# pengendali.net
KiCad netlist of a schematic drawn in EAGLE
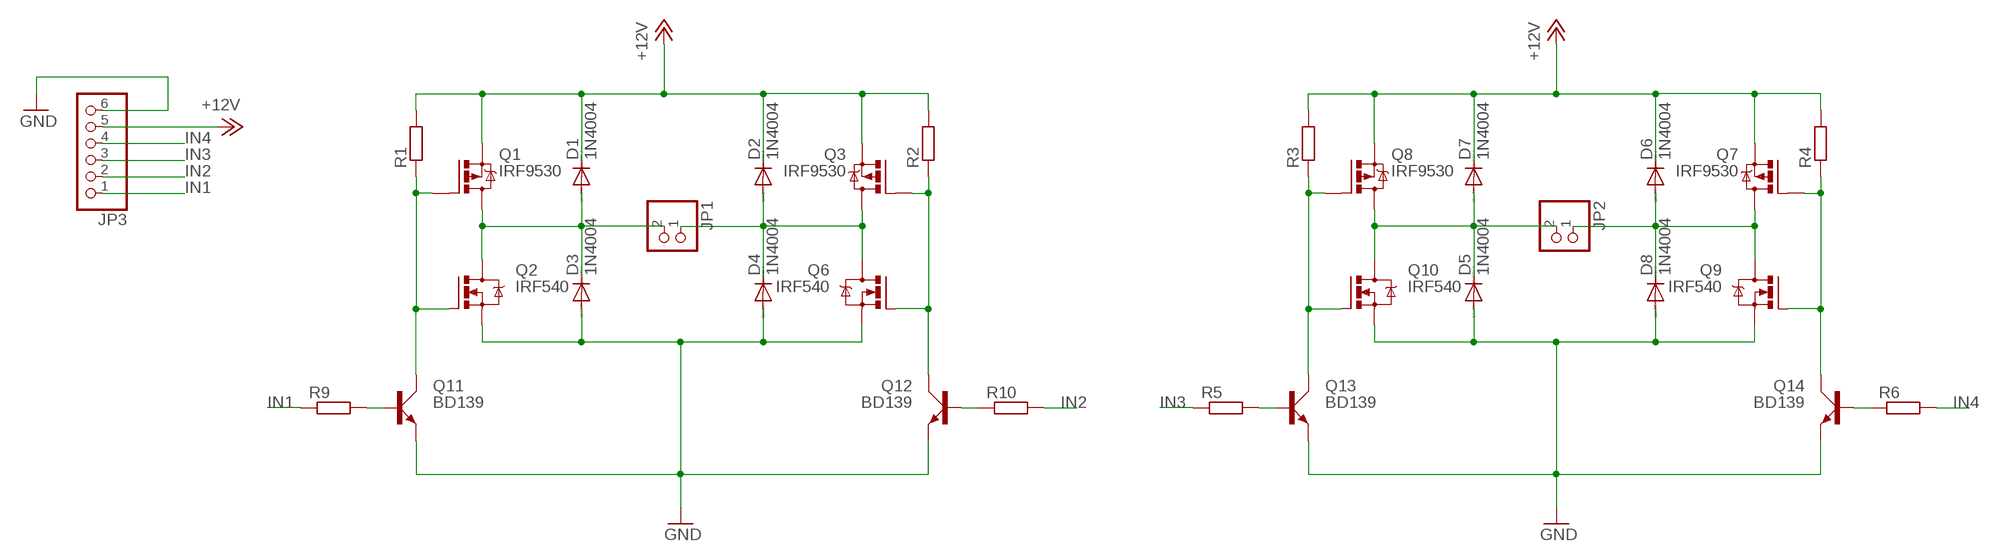
[diagram p0: schematic, sheet 1]

(export (version "E")
  (design (tool "Eeschema 10.0.6"))
  (components
    (comp (ref "D1")
      (value "1N4004")
      (footprint "eagle-import:DO41-10")
      (libsource (lib "eagle-import") (part "1N4004"))
    )
    (comp (ref "D2")
      (value "1N4004")
      (footprint "eagle-import:DO41-10")
      (libsource (lib "eagle-import") (part "1N4004"))
    )
    (comp (ref "D3")
      (value "1N4004")
      (footprint "eagle-import:DO41-10")
      (libsource (lib "eagle-import") (part "1N4004"))
    )
    (comp (ref "D4")
      (value "1N4004")
      (footprint "eagle-import:DO41-10")
      (libsource (lib "eagle-import") (part "1N4004"))
    )
    (comp (ref "D5")
      (value "1N4004")
      (footprint "eagle-import:DO41-10")
      (libsource (lib "eagle-import") (part "1N4004"))
    )
    (comp (ref "D6")
      (value "1N4004")
      (footprint "eagle-import:DO41-10")
      (libsource (lib "eagle-import") (part "1N4004"))
    )
    (comp (ref "D7")
      (value "1N4004")
      (footprint "eagle-import:DO41-10")
      (libsource (lib "eagle-import") (part "1N4004"))
    )
    (comp (ref "D8")
      (value "1N4004")
      (footprint "eagle-import:DO41-10")
      (libsource (lib "eagle-import") (part "1N4004"))
    )
    (comp (ref "JP1")
      (value "PINHD-1X2")
      (footprint "eagle-import:1X02")
      (libsource (lib "eagle-import") (part "PINHD-1X2"))
    )
    (comp (ref "JP2")
      (value "PINHD-1X2")
      (footprint "eagle-import:1X02")
      (libsource (lib "eagle-import") (part "PINHD-1X2"))
    )
    (comp (ref "JP3")
      (value "PINHD-1X6")
      (footprint "eagle-import:1X06")
      (libsource (lib "eagle-import") (part "PINHD-1X6"))
    )
    (comp (ref "Q1")
      (value "IRF9530")
      (footprint "eagle-import:TO220BV")
      (libsource (lib "eagle-import") (part "IRF9530"))
    )
    (comp (ref "Q2")
      (value "IRF540")
      (footprint "eagle-import:TO220BV")
      (libsource (lib "eagle-import") (part "IRF540"))
    )
    (comp (ref "Q3")
      (value "IRF9530")
      (footprint "eagle-import:TO220BV")
      (libsource (lib "eagle-import") (part "IRF9530"))
    )
    (comp (ref "Q6")
      (value "IRF540")
      (footprint "eagle-import:TO220BV")
      (libsource (lib "eagle-import") (part "IRF540"))
    )
    (comp (ref "Q7")
      (value "IRF9530")
      (footprint "eagle-import:TO220BV")
      (libsource (lib "eagle-import") (part "IRF9530"))
    )
    (comp (ref "Q8")
      (value "IRF9530")
      (footprint "eagle-import:TO220BV")
      (libsource (lib "eagle-import") (part "IRF9530"))
    )
    (comp (ref "Q9")
      (value "IRF540")
      (footprint "eagle-import:TO220BV")
      (libsource (lib "eagle-import") (part "IRF540"))
    )
    (comp (ref "Q10")
      (value "IRF540")
      (footprint "eagle-import:TO220BV")
      (libsource (lib "eagle-import") (part "IRF540"))
    )
    (comp (ref "Q11")
      (value "BD139")
      (footprint "eagle-import:TO126AV")
      (libsource (lib "eagle-import") (part "BD139"))
    )
    (comp (ref "Q12")
      (value "BD139")
      (footprint "eagle-import:TO126AV")
      (libsource (lib "eagle-import") (part "BD139"))
    )
    (comp (ref "Q13")
      (value "BD139")
      (footprint "eagle-import:TO126AV")
      (libsource (lib "eagle-import") (part "BD139"))
    )
    (comp (ref "Q14")
      (value "BD139")
      (footprint "eagle-import:TO126AV")
      (libsource (lib "eagle-import") (part "BD139"))
    )
    (comp (ref "R1")
      (value "R-EU_0204/7")
      (footprint "eagle-import:0204_7")
      (libsource (lib "eagle-import") (part "R-EU_0204/7"))
    )
    (comp (ref "R2")
      (value "R-EU_0204/7")
      (footprint "eagle-import:0204_7")
      (libsource (lib "eagle-import") (part "R-EU_0204/7"))
    )
    (comp (ref "R3")
      (value "R-EU_0204/7")
      (footprint "eagle-import:0204_7")
      (libsource (lib "eagle-import") (part "R-EU_0204/7"))
    )
    (comp (ref "R4")
      (value "R-EU_0204/7")
      (footprint "eagle-import:0204_7")
      (libsource (lib "eagle-import") (part "R-EU_0204/7"))
    )
    (comp (ref "R5")
      (value "R-EU_0204/7")
      (footprint "eagle-import:0204_7")
      (libsource (lib "eagle-import") (part "R-EU_0204/7"))
    )
    (comp (ref "R6")
      (value "R-EU_0204/7")
      (footprint "eagle-import:0204_7")
      (libsource (lib "eagle-import") (part "R-EU_0204/7"))
    )
    (comp (ref "R9")
      (value "R-EU_0204/7")
      (footprint "eagle-import:0204_7")
      (libsource (lib "eagle-import") (part "R-EU_0204/7"))
    )
    (comp (ref "R10")
      (value "R-EU_0204/7")
      (footprint "eagle-import:0204_7")
      (libsource (lib "eagle-import") (part "R-EU_0204/7"))
    )
  )
  (nets
    (net (code "1") (name "+12V") (class "Default")
      (node (ref "D1") (pin "C") (pinfunction "C_C") (pintype "passive"))
      (node (ref "D2") (pin "C") (pinfunction "C_C") (pintype "passive"))
      (node (ref "D6") (pin "C") (pinfunction "C_C") (pintype "passive"))
      (node (ref "D7") (pin "C") (pinfunction "C_C") (pintype "passive"))
      (node (ref "JP3") (pin "5") (pinfunction "5_5") (pintype "passive"))
      (node (ref "Q1") (pin "S") (pinfunction "S_S") (pintype "passive"))
      (node (ref "Q3") (pin "S") (pinfunction "S_S") (pintype "passive"))
      (node (ref "Q7") (pin "S") (pinfunction "S_S") (pintype "passive"))
      (node (ref "Q8") (pin "S") (pinfunction "S_S") (pintype "passive"))
      (node (ref "R1") (pin "2") (pinfunction "2_2") (pintype "passive"))
      (node (ref "R2") (pin "2") (pinfunction "2_2") (pintype "passive"))
      (node (ref "R3") (pin "2") (pinfunction "2_2") (pintype "passive"))
      (node (ref "R4") (pin "2") (pinfunction "2_2") (pintype "passive"))
    )
    (net (code "2") (name "/IN1") (class "Default")
      (node (ref "JP3") (pin "1") (pinfunction "1_1") (pintype "passive"))
      (node (ref "R9") (pin "1") (pinfunction "1_1") (pintype "passive"))
    )
    (net (code "3") (name "/IN2") (class "Default")
      (node (ref "JP3") (pin "2") (pinfunction "2_2") (pintype "passive"))
      (node (ref "R10") (pin "2") (pinfunction "2_2") (pintype "passive"))
    )
    (net (code "4") (name "/IN3") (class "Default")
      (node (ref "JP3") (pin "3") (pinfunction "3_3") (pintype "passive"))
      (node (ref "R5") (pin "1") (pinfunction "1_1") (pintype "passive"))
    )
    (net (code "5") (name "/IN4") (class "Default")
      (node (ref "JP3") (pin "4") (pinfunction "4_4") (pintype "passive"))
      (node (ref "R6") (pin "2") (pinfunction "2_2") (pintype "passive"))
    )
    (net (code "6") (name "GND") (class "Default")
      (node (ref "D3") (pin "A") (pinfunction "A_A") (pintype "passive"))
      (node (ref "D4") (pin "A") (pinfunction "A_A") (pintype "passive"))
      (node (ref "D5") (pin "A") (pinfunction "A_A") (pintype "passive"))
      (node (ref "D8") (pin "A") (pinfunction "A_A") (pintype "passive"))
      (node (ref "JP3") (pin "6") (pinfunction "6_6") (pintype "passive"))
      (node (ref "Q10") (pin "S") (pinfunction "S_S") (pintype "passive"))
      (node (ref "Q11") (pin "E") (pinfunction "E_E") (pintype "passive"))
      (node (ref "Q12") (pin "E") (pinfunction "E_E") (pintype "passive"))
      (node (ref "Q13") (pin "E") (pinfunction "E_E") (pintype "passive"))
      (node (ref "Q14") (pin "E") (pinfunction "E_E") (pintype "passive"))
      (node (ref "Q2") (pin "S") (pinfunction "S_S") (pintype "passive"))
      (node (ref "Q6") (pin "S") (pinfunction "S_S") (pintype "passive"))
      (node (ref "Q9") (pin "S") (pinfunction "S_S") (pintype "passive"))
    )
    (net (code "7") (name "Net-(D1-PadA)") (class "Default")
      (node (ref "D1") (pin "A") (pinfunction "A_A") (pintype "passive"))
      (node (ref "D3") (pin "C") (pinfunction "C_C") (pintype "passive"))
      (node (ref "JP1") (pin "2") (pinfunction "2_2") (pintype "passive"))
      (node (ref "Q1") (pin "D") (pinfunction "D_D") (pintype "passive"))
      (node (ref "Q2") (pin "D") (pinfunction "D_D") (pintype "passive"))
    )
    (net (code "8") (name "Net-(D2-PadA)") (class "Default")
      (node (ref "D2") (pin "A") (pinfunction "A_A") (pintype "passive"))
      (node (ref "D4") (pin "C") (pinfunction "C_C") (pintype "passive"))
      (node (ref "JP1") (pin "1") (pinfunction "1_1") (pintype "passive"))
      (node (ref "Q3") (pin "D") (pinfunction "D_D") (pintype "passive"))
      (node (ref "Q6") (pin "D") (pinfunction "D_D") (pintype "passive"))
    )
    (net (code "9") (name "Net-(D5-PadC)") (class "Default")
      (node (ref "D5") (pin "C") (pinfunction "C_C") (pintype "passive"))
      (node (ref "D7") (pin "A") (pinfunction "A_A") (pintype "passive"))
      (node (ref "JP2") (pin "2") (pinfunction "2_2") (pintype "passive"))
      (node (ref "Q10") (pin "D") (pinfunction "D_D") (pintype "passive"))
      (node (ref "Q8") (pin "D") (pinfunction "D_D") (pintype "passive"))
    )
    (net (code "10") (name "Net-(D6-PadA)") (class "Default")
      (node (ref "D6") (pin "A") (pinfunction "A_A") (pintype "passive"))
      (node (ref "D8") (pin "C") (pinfunction "C_C") (pintype "passive"))
      (node (ref "JP2") (pin "1") (pinfunction "1_1") (pintype "passive"))
      (node (ref "Q7") (pin "D") (pinfunction "D_D") (pintype "passive"))
      (node (ref "Q9") (pin "D") (pinfunction "D_D") (pintype "passive"))
    )
    (net (code "11") (name "Net-(Q1-PadG)") (class "Default")
      (node (ref "Q1") (pin "G") (pinfunction "G_G") (pintype "passive"))
      (node (ref "Q11") (pin "C") (pinfunction "C_C") (pintype "passive"))
      (node (ref "Q2") (pin "G") (pinfunction "G_G") (pintype "passive"))
      (node (ref "R1") (pin "1") (pinfunction "1_1") (pintype "passive"))
    )
    (net (code "12") (name "Net-(Q10-PadG)") (class "Default")
      (node (ref "Q10") (pin "G") (pinfunction "G_G") (pintype "passive"))
      (node (ref "Q13") (pin "C") (pinfunction "C_C") (pintype "passive"))
      (node (ref "Q8") (pin "G") (pinfunction "G_G") (pintype "passive"))
      (node (ref "R3") (pin "1") (pinfunction "1_1") (pintype "passive"))
    )
    (net (code "13") (name "Net-(Q11-PadB)") (class "Default")
      (node (ref "Q11") (pin "B") (pinfunction "B_B") (pintype "passive"))
      (node (ref "R9") (pin "2") (pinfunction "2_2") (pintype "passive"))
    )
    (net (code "14") (name "Net-(Q12-PadB)") (class "Default")
      (node (ref "Q12") (pin "B") (pinfunction "B_B") (pintype "passive"))
      (node (ref "R10") (pin "1") (pinfunction "1_1") (pintype "passive"))
    )
    (net (code "15") (name "Net-(Q12-PadC)") (class "Default")
      (node (ref "Q12") (pin "C") (pinfunction "C_C") (pintype "passive"))
      (node (ref "Q3") (pin "G") (pinfunction "G_G") (pintype "passive"))
      (node (ref "Q6") (pin "G") (pinfunction "G_G") (pintype "passive"))
      (node (ref "R2") (pin "1") (pinfunction "1_1") (pintype "passive"))
    )
    (net (code "16") (name "Net-(Q13-PadB)") (class "Default")
      (node (ref "Q13") (pin "B") (pinfunction "B_B") (pintype "passive"))
      (node (ref "R5") (pin "2") (pinfunction "2_2") (pintype "passive"))
    )
    (net (code "17") (name "Net-(Q14-PadB)") (class "Default")
      (node (ref "Q14") (pin "B") (pinfunction "B_B") (pintype "passive"))
      (node (ref "R6") (pin "1") (pinfunction "1_1") (pintype "passive"))
    )
    (net (code "18") (name "Net-(Q14-PadC)") (class "Default")
      (node (ref "Q14") (pin "C") (pinfunction "C_C") (pintype "passive"))
      (node (ref "Q7") (pin "G") (pinfunction "G_G") (pintype "passive"))
      (node (ref "Q9") (pin "G") (pinfunction "G_G") (pintype "passive"))
      (node (ref "R4") (pin "1") (pinfunction "1_1") (pintype "passive"))
    )
  )
)
